# Netzteil-Treiber.net
KiCad netlist of a schematic drawn in EAGLE
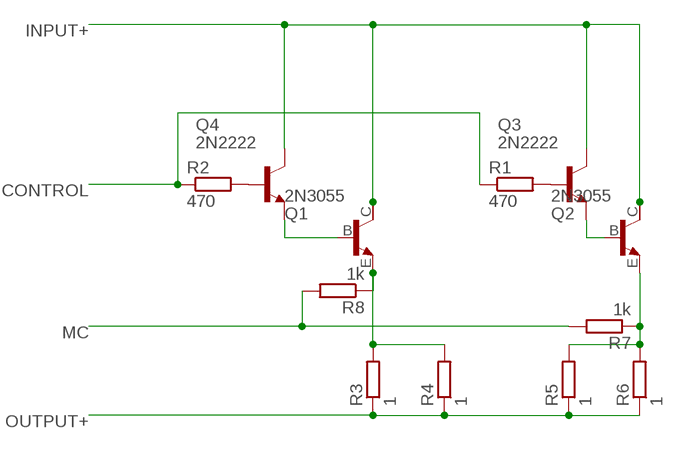
[diagram p0: schematic, sheet 1]

(export (version "E")
  (design (tool "Eeschema 10.0.6"))
  (components
    (comp (ref "Q1")
      (value "2N3055")
      (footprint "eagle-import:TO3")
      (libsource (lib "eagle-import") (part "2N3055"))
    )
    (comp (ref "Q2")
      (value "2N3055")
      (footprint "eagle-import:TO3")
      (libsource (lib "eagle-import") (part "2N3055"))
    )
    (comp (ref "Q3")
      (value "2N2222")
      (footprint "eagle-import:TO18")
      (libsource (lib "eagle-import") (part "2N2222"))
    )
    (comp (ref "Q4")
      (value "2N2222")
      (footprint "eagle-import:TO18")
      (libsource (lib "eagle-import") (part "2N2222"))
    )
    (comp (ref "R1")
      (value "470")
      (footprint "eagle-import:0207_12")
      (libsource (lib "eagle-import") (part "R-EU_0207/12"))
    )
    (comp (ref "R2")
      (value "470")
      (footprint "eagle-import:0207_12")
      (libsource (lib "eagle-import") (part "R-EU_0207/12"))
    )
    (comp (ref "R3")
      (value "1")
      (footprint "eagle-import:0207_12")
      (libsource (lib "eagle-import") (part "R-EU_0207/12"))
    )
    (comp (ref "R4")
      (value "1")
      (footprint "eagle-import:0207_12")
      (libsource (lib "eagle-import") (part "R-EU_0207/12"))
    )
    (comp (ref "R5")
      (value "1")
      (footprint "eagle-import:0207_12")
      (libsource (lib "eagle-import") (part "R-EU_0207/12"))
    )
    (comp (ref "R6")
      (value "1")
      (footprint "eagle-import:0207_12")
      (libsource (lib "eagle-import") (part "R-EU_0207/12"))
    )
    (comp (ref "R7")
      (value "1k")
      (footprint "eagle-import:0207_12")
      (libsource (lib "eagle-import") (part "R-EU_0207/12"))
    )
    (comp (ref "R8")
      (value "1k")
      (footprint "eagle-import:0207_12")
      (libsource (lib "eagle-import") (part "R-EU_0207/12"))
    )
  )
  (nets
    (net (code "1") (name "/CONTROL") (class "Default")
      (node (ref "R1") (pin "1") (pinfunction "1_1") (pintype "passive"))
      (node (ref "R2") (pin "1") (pinfunction "1_1") (pintype "passive"))
    )
    (net (code "2") (name "/INPUT+") (class "Default")
      (node (ref "Q1") (pin "C") (pinfunction "C_C") (pintype "passive"))
      (node (ref "Q2") (pin "C") (pinfunction "C_C") (pintype "passive"))
      (node (ref "Q3") (pin "3") (pinfunction "C_3") (pintype "passive"))
      (node (ref "Q4") (pin "3") (pinfunction "C_3") (pintype "passive"))
    )
    (net (code "3") (name "/MC") (class "Default")
      (node (ref "R7") (pin "2") (pinfunction "2_2") (pintype "passive"))
      (node (ref "R8") (pin "2") (pinfunction "2_2") (pintype "passive"))
    )
    (net (code "4") (name "/OUTPUT+") (class "Default")
      (node (ref "R3") (pin "1") (pinfunction "1_1") (pintype "passive"))
      (node (ref "R4") (pin "1") (pinfunction "1_1") (pintype "passive"))
      (node (ref "R5") (pin "1") (pinfunction "1_1") (pintype "passive"))
      (node (ref "R6") (pin "1") (pinfunction "1_1") (pintype "passive"))
    )
    (net (code "5") (name "Net-(Q1-PadE)") (class "Default")
      (node (ref "Q1") (pin "E") (pinfunction "E_E") (pintype "passive"))
      (node (ref "R3") (pin "2") (pinfunction "2_2") (pintype "passive"))
      (node (ref "R4") (pin "2") (pinfunction "2_2") (pintype "passive"))
      (node (ref "R8") (pin "1") (pinfunction "1_1") (pintype "passive"))
    )
    (net (code "6") (name "Net-(Q2-PadE)") (class "Default")
      (node (ref "Q2") (pin "E") (pinfunction "E_E") (pintype "passive"))
      (node (ref "R5") (pin "2") (pinfunction "2_2") (pintype "passive"))
      (node (ref "R6") (pin "2") (pinfunction "2_2") (pintype "passive"))
      (node (ref "R7") (pin "1") (pinfunction "1_1") (pintype "passive"))
    )
    (net (code "7") (name "Net-(Q3-B)") (class "Default")
      (node (ref "Q3") (pin "2") (pinfunction "B_2") (pintype "passive"))
      (node (ref "R1") (pin "2") (pinfunction "2_2") (pintype "passive"))
    )
    (net (code "8") (name "Net-(Q3-E)") (class "Default")
      (node (ref "Q2") (pin "B") (pinfunction "B_B") (pintype "passive"))
      (node (ref "Q3") (pin "1") (pinfunction "E_1") (pintype "passive"))
    )
    (net (code "9") (name "Net-(Q4-B)") (class "Default")
      (node (ref "Q4") (pin "2") (pinfunction "B_2") (pintype "passive"))
      (node (ref "R2") (pin "2") (pinfunction "2_2") (pintype "passive"))
    )
    (net (code "10") (name "Net-(Q4-E)") (class "Default")
      (node (ref "Q1") (pin "B") (pinfunction "B_B") (pintype "passive"))
      (node (ref "Q4") (pin "1") (pinfunction "E_1") (pintype "passive"))
    )
    (net (code "11") (name "unconnected-(Q1-C-PadC{slash})") (class "Default")
      (node (ref "Q1") (pin "C/") (pinfunction "C_C/") (pintype "passive"))
    )
    (net (code "12") (name "unconnected-(Q2-C-PadC{slash})") (class "Default")
      (node (ref "Q2") (pin "C/") (pinfunction "C_C/") (pintype "passive"))
    )
  )
)
